# slave.net
KiCad netlist of a schematic drawn in EAGLE
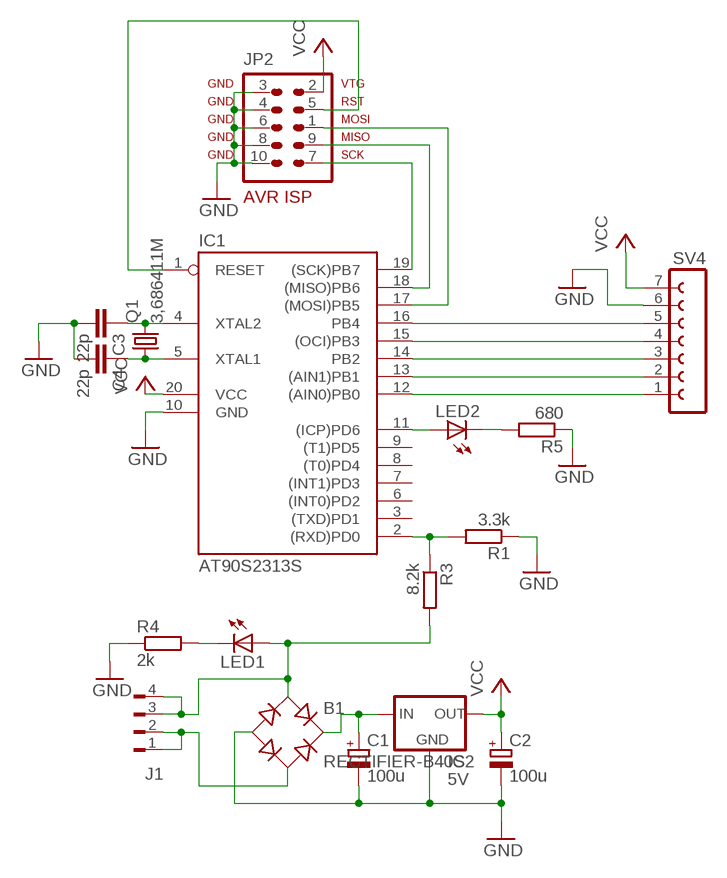
[diagram p0: schematic, sheet 1]

(export (version "E")
  (design (tool "Eeschema 10.0.6"))
  (components
    (comp (ref "B1")
      (value "RECTIFIER-B40S")
      (footprint "eagle-import:B40S")
      (libsource (lib "eagle-import") (part "RECTIFIER-B40S"))
    )
    (comp (ref "C1")
      (value "100u")
      (footprint "eagle-import:E2,5-6")
      (libsource (lib "eagle-import") (part "CPOL-EUE2.5-6"))
    )
    (comp (ref "C2")
      (value "100u")
      (footprint "eagle-import:E2,5-6")
      (libsource (lib "eagle-import") (part "CPOL-EUE2.5-6"))
    )
    (comp (ref "C3")
      (value "22p")
      (footprint "eagle-import:C025-025X050")
      (libsource (lib "eagle-import") (part "C-EU025-025X050"))
    )
    (comp (ref "C4")
      (value "22p")
      (footprint "eagle-import:C025-025X050")
      (libsource (lib "eagle-import") (part "C-EU025-025X050"))
    )
    (comp (ref "IC1")
      (value "AT90S2313S")
      (footprint "eagle-import:SO20L")
      (libsource (lib "eagle-import") (part "AT90S2313S"))
    )
    (comp (ref "IC2")
      (value "5V")
      (footprint "eagle-import:78XXS")
      (libsource (lib "eagle-import") (part "78XXS"))
    )
    (comp (ref "J1")
      (value "FLOPPY-4")
      (footprint "eagle-import:FLOPPY-4")
      (libsource (lib "eagle-import") (part "FLOPPY-4"))
    )
    (comp (ref "JP2")
      (value "AVR-ISP-10")
      (footprint "eagle-import:AVR-ISP-10")
      (libsource (lib "eagle-import") (part "AVR-ISP-10"))
    )
    (comp (ref "LED1")
      (value "LED3MM")
      (footprint "eagle-import:LED3MM")
      (libsource (lib "eagle-import") (part "LED3MM"))
    )
    (comp (ref "LED2")
      (value "LED3MM")
      (footprint "eagle-import:LED3MM")
      (libsource (lib "eagle-import") (part "LED3MM"))
    )
    (comp (ref "Q1")
      (value "3,686411M")
      (footprint "eagle-import:HC49U-V")
      (libsource (lib "eagle-import") (part "CRYSTALHC49U-V"))
    )
    (comp (ref "R1")
      (value "3.3k")
      (footprint "eagle-import:R1206W")
      (libsource (lib "eagle-import") (part "R-EU_R1206W"))
    )
    (comp (ref "R3")
      (value "8.2k")
      (footprint "eagle-import:R1206W")
      (libsource (lib "eagle-import") (part "R-EU_R1206W"))
    )
    (comp (ref "R4")
      (value "2k")
      (footprint "eagle-import:R1206W")
      (libsource (lib "eagle-import") (part "R-EU_R1206W"))
    )
    (comp (ref "R5")
      (value "680")
      (footprint "eagle-import:R1206W")
      (libsource (lib "eagle-import") (part "R-EU_R1206W"))
    )
    (comp (ref "SV4")
      (value "FE07-1")
      (footprint "eagle-import:FE07")
      (libsource (lib "eagle-import") (part "FE07-1"))
    )
  )
  (nets
    (net (code "1") (name "GND") (class "Default")
      (node (ref "B1") (pin "-") (pinfunction "-_-") (pintype "passive"))
      (node (ref "C1") (pin "-") (pinfunction "-_-") (pintype "passive"))
      (node (ref "C2") (pin "-") (pinfunction "-_-") (pintype "passive"))
      (node (ref "C3") (pin "2") (pinfunction "2_2") (pintype "passive"))
      (node (ref "C4") (pin "2") (pinfunction "2_2") (pintype "passive"))
      (node (ref "IC1") (pin "10") (pinfunction "GND_10") (pintype "power_in"))
      (node (ref "IC2") (pin "GND") (pinfunction "GND_GND") (pintype "input"))
      (node (ref "JP2") (pin "10") (pinfunction "10_10") (pintype "passive"))
      (node (ref "JP2") (pin "3") (pinfunction "3_3") (pintype "passive"))
      (node (ref "JP2") (pin "4") (pinfunction "4_4") (pintype "passive"))
      (node (ref "JP2") (pin "6") (pinfunction "6_6") (pintype "passive"))
      (node (ref "JP2") (pin "8") (pinfunction "8_8") (pintype "passive"))
      (node (ref "R1") (pin "1") (pinfunction "1_1") (pintype "passive"))
      (node (ref "R4") (pin "1") (pinfunction "1_1") (pintype "passive"))
      (node (ref "R5") (pin "1") (pinfunction "1_1") (pintype "passive"))
      (node (ref "SV4") (pin "6") (pinfunction "6_6") (pintype "passive"))
    )
    (net (code "2") (name "Net-(B1-Pad+)") (class "Default")
      (node (ref "B1") (pin "+") (pinfunction "+_+") (pintype "passive"))
      (node (ref "C1") (pin "+") (pinfunction "+_+") (pintype "passive"))
      (node (ref "IC2") (pin "IN") (pinfunction "IN_IN") (pintype "input"))
    )
    (net (code "3") (name "Net-(B1-PadAC1)") (class "Default")
      (node (ref "B1") (pin "AC1") (pinfunction "AC1_AC1") (pintype "passive"))
      (node (ref "J1") (pin "3") (pinfunction "3_3") (pintype "passive"))
      (node (ref "J1") (pin "4") (pinfunction "4_4") (pintype "passive"))
      (node (ref "LED1") (pin "A") (pinfunction "A_A") (pintype "passive"))
      (node (ref "R3") (pin "2") (pinfunction "2_2") (pintype "passive"))
    )
    (net (code "4") (name "Net-(B1-PadAC2)") (class "Default")
      (node (ref "B1") (pin "AC2") (pinfunction "AC2_AC2") (pintype "passive"))
      (node (ref "J1") (pin "1") (pinfunction "1_1") (pintype "passive"))
      (node (ref "J1") (pin "2") (pinfunction "2_2") (pintype "passive"))
    )
    (net (code "5") (name "Net-(IC1-(AIN0)PB0)") (class "Default")
      (node (ref "IC1") (pin "12") (pinfunction "(AIN0)PB0_12") (pintype "bidirectional"))
      (node (ref "SV4") (pin "1") (pinfunction "1_1") (pintype "passive"))
    )
    (net (code "6") (name "Net-(IC1-(AIN1)PB1)") (class "Default")
      (node (ref "IC1") (pin "13") (pinfunction "(AIN1)PB1_13") (pintype "bidirectional"))
      (node (ref "SV4") (pin "2") (pinfunction "2_2") (pintype "passive"))
    )
    (net (code "7") (name "Net-(IC1-(ICP)PD6)") (class "Default")
      (node (ref "IC1") (pin "11") (pinfunction "(ICP)PD6_11") (pintype "bidirectional"))
      (node (ref "LED2") (pin "A") (pinfunction "A_A") (pintype "passive"))
    )
    (net (code "8") (name "Net-(IC1-(MISO)PB6)") (class "Default")
      (node (ref "IC1") (pin "18") (pinfunction "(MISO)PB6_18") (pintype "bidirectional"))
      (node (ref "JP2") (pin "9") (pinfunction "9_9") (pintype "passive"))
    )
    (net (code "9") (name "Net-(IC1-(MOSI)PB5)") (class "Default")
      (node (ref "IC1") (pin "17") (pinfunction "(MOSI)PB5_17") (pintype "bidirectional"))
      (node (ref "JP2") (pin "1") (pinfunction "1_1") (pintype "passive"))
    )
    (net (code "10") (name "Net-(IC1-(OCI)PB3)") (class "Default")
      (node (ref "IC1") (pin "15") (pinfunction "(OCI)PB3_15") (pintype "bidirectional"))
      (node (ref "SV4") (pin "4") (pinfunction "4_4") (pintype "passive"))
    )
    (net (code "11") (name "Net-(IC1-(RXD)PD0)") (class "Default")
      (node (ref "IC1") (pin "2") (pinfunction "(RXD)PD0_2") (pintype "bidirectional"))
      (node (ref "R1") (pin "2") (pinfunction "2_2") (pintype "passive"))
      (node (ref "R3") (pin "1") (pinfunction "1_1") (pintype "passive"))
    )
    (net (code "12") (name "Net-(IC1-(SCK)PB7)") (class "Default")
      (node (ref "IC1") (pin "19") (pinfunction "(SCK)PB7_19") (pintype "bidirectional"))
      (node (ref "JP2") (pin "7") (pinfunction "7_7") (pintype "passive"))
    )
    (net (code "13") (name "Net-(IC1-PB2)") (class "Default")
      (node (ref "IC1") (pin "14") (pinfunction "PB2_14") (pintype "bidirectional"))
      (node (ref "SV4") (pin "3") (pinfunction "3_3") (pintype "passive"))
    )
    (net (code "14") (name "Net-(IC1-PB4)") (class "Default")
      (node (ref "IC1") (pin "16") (pinfunction "PB4_16") (pintype "bidirectional"))
      (node (ref "SV4") (pin "5") (pinfunction "5_5") (pintype "passive"))
    )
    (net (code "15") (name "Net-(IC1-RESET)") (class "Default")
      (node (ref "IC1") (pin "1") (pinfunction "RESET_1") (pintype "bidirectional"))
      (node (ref "JP2") (pin "5") (pinfunction "5_5") (pintype "passive"))
    )
    (net (code "16") (name "Net-(IC1-XTAL1)") (class "Default")
      (node (ref "C4") (pin "1") (pinfunction "1_1") (pintype "passive"))
      (node (ref "IC1") (pin "5") (pinfunction "XTAL1_5") (pintype "bidirectional"))
      (node (ref "Q1") (pin "1") (pinfunction "1_1") (pintype "passive"))
    )
    (net (code "17") (name "Net-(IC1-XTAL2)") (class "Default")
      (node (ref "C3") (pin "1") (pinfunction "1_1") (pintype "passive"))
      (node (ref "IC1") (pin "4") (pinfunction "XTAL2_4") (pintype "bidirectional"))
      (node (ref "Q1") (pin "2") (pinfunction "2_2") (pintype "passive"))
    )
    (net (code "18") (name "Net-(LED1-C)") (class "Default")
      (node (ref "LED1") (pin "K") (pinfunction "C_K") (pintype "passive"))
      (node (ref "R4") (pin "2") (pinfunction "2_2") (pintype "passive"))
    )
    (net (code "19") (name "Net-(LED2-C)") (class "Default")
      (node (ref "LED2") (pin "K") (pinfunction "C_K") (pintype "passive"))
      (node (ref "R5") (pin "2") (pinfunction "2_2") (pintype "passive"))
    )
    (net (code "20") (name "VCC") (class "Default")
      (node (ref "C2") (pin "+") (pinfunction "+_+") (pintype "passive"))
      (node (ref "IC1") (pin "20") (pinfunction "VCC_20") (pintype "power_in"))
      (node (ref "IC2") (pin "OUT") (pinfunction "OUT_OUT") (pintype "passive"))
      (node (ref "JP2") (pin "2") (pinfunction "2_2") (pintype "passive"))
      (node (ref "SV4") (pin "7") (pinfunction "7_7") (pintype "passive"))
    )
    (net (code "21") (name "unconnected-(IC1-(INT0)PD2-Pad6)") (class "Default")
      (node (ref "IC1") (pin "6") (pinfunction "(INT0)PD2_6") (pintype "bidirectional"))
    )
    (net (code "22") (name "unconnected-(IC1-(INT1)PD3-Pad7)") (class "Default")
      (node (ref "IC1") (pin "7") (pinfunction "(INT1)PD3_7") (pintype "bidirectional"))
    )
    (net (code "23") (name "unconnected-(IC1-(T0)PD4-Pad8)") (class "Default")
      (node (ref "IC1") (pin "8") (pinfunction "(T0)PD4_8") (pintype "bidirectional"))
    )
    (net (code "24") (name "unconnected-(IC1-(T1)PD5-Pad9)") (class "Default")
      (node (ref "IC1") (pin "9") (pinfunction "(T1)PD5_9") (pintype "bidirectional"))
    )
    (net (code "25") (name "unconnected-(IC1-(TXD)PD1-Pad3)") (class "Default")
      (node (ref "IC1") (pin "3") (pinfunction "(TXD)PD1_3") (pintype "bidirectional"))
    )
  )
)
